# a4988-driver-arduino-shield-v1.net
KiCad netlist of a schematic drawn in EAGLE
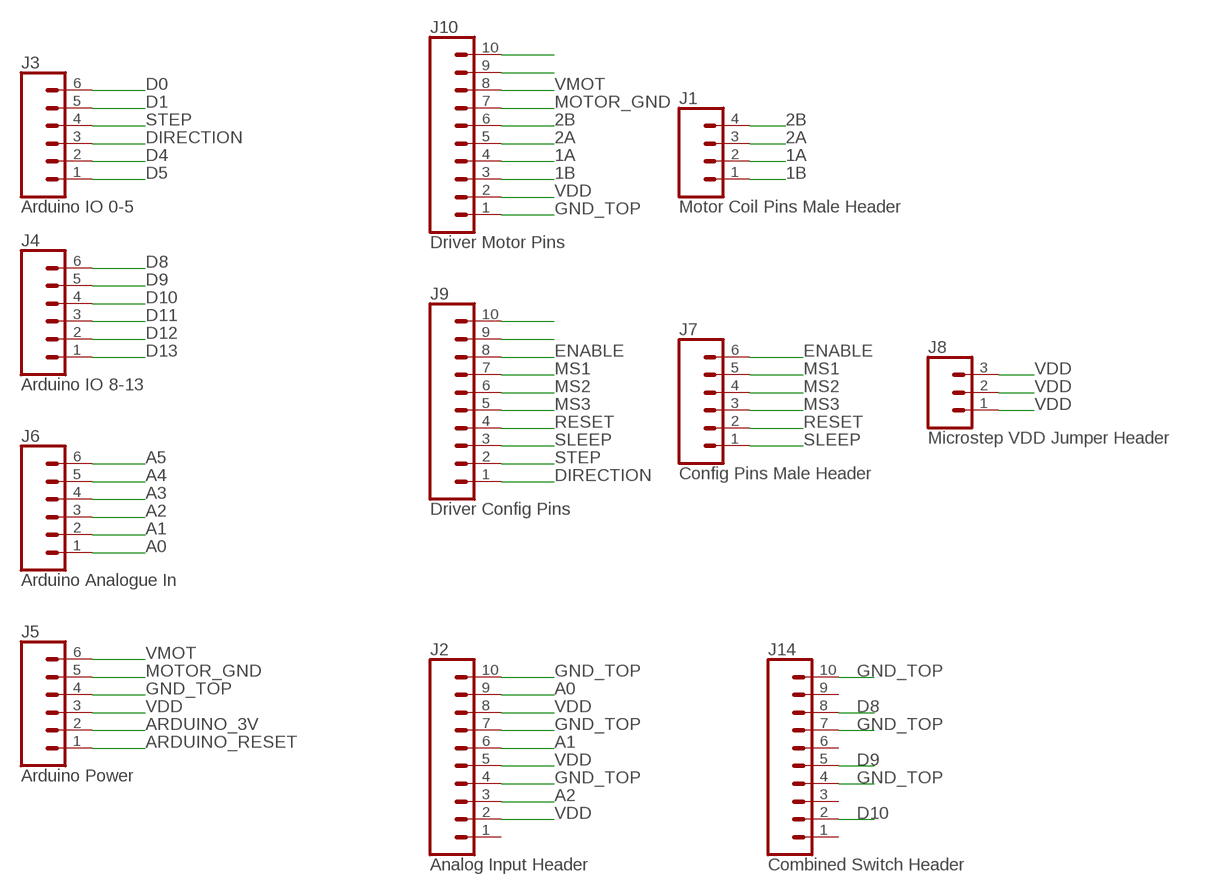
[diagram p0: schematic, sheet 1]

(export (version "E")
  (design (tool "Eeschema 10.0.6"))
  (components
    (comp (ref "J1")
      (value "Motor Coil Pins Male Header")
      (footprint "eagle-import:1X04_LONGPADS")
      (libsource (lib "eagle-import") (part "CONN_04LONGPADS"))
    )
    (comp (ref "J2")
      (value "Analog Input Header")
      (footprint "eagle-import:1X10_SMD_MALE")
      (libsource (lib "eagle-import") (part "CONN_10SMD_MALE"))
    )
    (comp (ref "J3")
      (value "Arduino IO 0-5")
      (footprint "eagle-import:1X06_NO_SILK")
      (libsource (lib "eagle-import") (part "CONN_06NO_SILK_FEMALE_PTH"))
    )
    (comp (ref "J4")
      (value "Arduino IO 8-13")
      (footprint "eagle-import:1X06_NO_SILK")
      (libsource (lib "eagle-import") (part "CONN_06NO_SILK_FEMALE_PTH"))
    )
    (comp (ref "J5")
      (value "Arduino Power")
      (footprint "eagle-import:1X06_NO_SILK")
      (libsource (lib "eagle-import") (part "CONN_06NO_SILK_FEMALE_PTH"))
    )
    (comp (ref "J6")
      (value "Arduino Analogue In")
      (footprint "eagle-import:1X06_NO_SILK")
      (libsource (lib "eagle-import") (part "CONN_06NO_SILK_FEMALE_PTH"))
    )
    (comp (ref "J7")
      (value "Config Pins Male Header")
      (footprint "eagle-import:1X06_SMD_MALE")
      (libsource (lib "eagle-import") (part "CONN_06SMD_MALE"))
    )
    (comp (ref "J8")
      (value "Microstep VDD Jumper Header")
      (footprint "eagle-import:1X03_LONGPADS")
      (libsource (lib "eagle-import") (part "CONN_03LONGPADS"))
    )
    (comp (ref "J9")
      (value "Driver Config Pins")
      (footprint "eagle-import:1X10_SMD_MALE")
      (libsource (lib "eagle-import") (part "CONN_10SMD_MALE"))
    )
    (comp (ref "J10")
      (value "Driver Motor Pins")
      (footprint "eagle-import:1X10_SMD_MALE")
      (libsource (lib "eagle-import") (part "CONN_10SMD_MALE"))
    )
    (comp (ref "J14")
      (value "Combined Switch Header")
      (footprint "eagle-import:1X10_SMD_MALE")
      (libsource (lib "eagle-import") (part "CONN_10SMD_MALE"))
    )
  )
  (nets
    (net (code "1") (name "/1A") (class "Default")
      (node (ref "J1") (pin "2") (pinfunction "2_2") (pintype "passive"))
      (node (ref "J10") (pin "4") (pinfunction "4_4") (pintype "passive"))
    )
    (net (code "2") (name "/1B") (class "Default")
      (node (ref "J1") (pin "1") (pinfunction "1_1") (pintype "passive"))
      (node (ref "J10") (pin "3") (pinfunction "3_3") (pintype "passive"))
    )
    (net (code "3") (name "/2A") (class "Default")
      (node (ref "J1") (pin "3") (pinfunction "3_3") (pintype "passive"))
      (node (ref "J10") (pin "5") (pinfunction "5_5") (pintype "passive"))
    )
    (net (code "4") (name "/2B") (class "Default")
      (node (ref "J1") (pin "4") (pinfunction "4_4") (pintype "passive"))
      (node (ref "J10") (pin "6") (pinfunction "6_6") (pintype "passive"))
    )
    (net (code "5") (name "/A0") (class "Default")
      (node (ref "J2") (pin "9") (pinfunction "9_9") (pintype "passive"))
      (node (ref "J6") (pin "1") (pinfunction "1_1") (pintype "passive"))
    )
    (net (code "6") (name "/A1") (class "Default")
      (node (ref "J2") (pin "6") (pinfunction "6_6") (pintype "passive"))
      (node (ref "J6") (pin "2") (pinfunction "2_2") (pintype "passive"))
    )
    (net (code "7") (name "/A2") (class "Default")
      (node (ref "J2") (pin "3") (pinfunction "3_3") (pintype "passive"))
      (node (ref "J6") (pin "3") (pinfunction "3_3") (pintype "passive"))
    )
    (net (code "8") (name "/A3") (class "Default")
      (node (ref "J6") (pin "4") (pinfunction "4_4") (pintype "passive"))
    )
    (net (code "9") (name "/A4") (class "Default")
      (node (ref "J6") (pin "5") (pinfunction "5_5") (pintype "passive"))
    )
    (net (code "10") (name "/A5") (class "Default")
      (node (ref "J6") (pin "6") (pinfunction "6_6") (pintype "passive"))
    )
    (net (code "11") (name "/ARDUINO_3V") (class "Default")
      (node (ref "J5") (pin "2") (pinfunction "2_2") (pintype "passive"))
    )
    (net (code "12") (name "/ARDUINO_RESET") (class "Default")
      (node (ref "J5") (pin "1") (pinfunction "1_1") (pintype "passive"))
    )
    (net (code "13") (name "/D0") (class "Default")
      (node (ref "J3") (pin "6") (pinfunction "6_6") (pintype "passive"))
    )
    (net (code "14") (name "/D1") (class "Default")
      (node (ref "J3") (pin "5") (pinfunction "5_5") (pintype "passive"))
    )
    (net (code "15") (name "/D4") (class "Default")
      (node (ref "J3") (pin "2") (pinfunction "2_2") (pintype "passive"))
    )
    (net (code "16") (name "/D5") (class "Default")
      (node (ref "J3") (pin "1") (pinfunction "1_1") (pintype "passive"))
    )
    (net (code "17") (name "/D8") (class "Default")
      (node (ref "J14") (pin "8") (pinfunction "8_8") (pintype "passive"))
      (node (ref "J4") (pin "6") (pinfunction "6_6") (pintype "passive"))
    )
    (net (code "18") (name "/D9") (class "Default")
      (node (ref "J14") (pin "5") (pinfunction "5_5") (pintype "passive"))
      (node (ref "J4") (pin "5") (pinfunction "5_5") (pintype "passive"))
    )
    (net (code "19") (name "/D10") (class "Default")
      (node (ref "J14") (pin "2") (pinfunction "2_2") (pintype "passive"))
      (node (ref "J4") (pin "4") (pinfunction "4_4") (pintype "passive"))
    )
    (net (code "20") (name "/D11") (class "Default")
      (node (ref "J4") (pin "3") (pinfunction "3_3") (pintype "passive"))
    )
    (net (code "21") (name "/D12") (class "Default")
      (node (ref "J4") (pin "2") (pinfunction "2_2") (pintype "passive"))
    )
    (net (code "22") (name "/D13") (class "Default")
      (node (ref "J4") (pin "1") (pinfunction "1_1") (pintype "passive"))
    )
    (net (code "23") (name "/DIRECTION") (class "Default")
      (node (ref "J3") (pin "3") (pinfunction "3_3") (pintype "passive"))
      (node (ref "J9") (pin "1") (pinfunction "1_1") (pintype "passive"))
    )
    (net (code "24") (name "/ENABLE") (class "Default")
      (node (ref "J7") (pin "6") (pinfunction "6_6") (pintype "passive"))
      (node (ref "J9") (pin "8") (pinfunction "8_8") (pintype "passive"))
    )
    (net (code "25") (name "/GND_TOP") (class "Default")
      (node (ref "J10") (pin "1") (pinfunction "1_1") (pintype "passive"))
      (node (ref "J14") (pin "10") (pinfunction "10_10") (pintype "passive"))
      (node (ref "J14") (pin "4") (pinfunction "4_4") (pintype "passive"))
      (node (ref "J14") (pin "7") (pinfunction "7_7") (pintype "passive"))
      (node (ref "J2") (pin "10") (pinfunction "10_10") (pintype "passive"))
      (node (ref "J2") (pin "4") (pinfunction "4_4") (pintype "passive"))
      (node (ref "J2") (pin "7") (pinfunction "7_7") (pintype "passive"))
      (node (ref "J5") (pin "4") (pinfunction "4_4") (pintype "passive"))
    )
    (net (code "26") (name "/MOTOR_GND") (class "Default")
      (node (ref "J10") (pin "7") (pinfunction "7_7") (pintype "passive"))
      (node (ref "J5") (pin "5") (pinfunction "5_5") (pintype "passive"))
    )
    (net (code "27") (name "/MS1") (class "Default")
      (node (ref "J7") (pin "5") (pinfunction "5_5") (pintype "passive"))
      (node (ref "J9") (pin "7") (pinfunction "7_7") (pintype "passive"))
    )
    (net (code "28") (name "/MS2") (class "Default")
      (node (ref "J7") (pin "4") (pinfunction "4_4") (pintype "passive"))
      (node (ref "J9") (pin "6") (pinfunction "6_6") (pintype "passive"))
    )
    (net (code "29") (name "/MS3") (class "Default")
      (node (ref "J7") (pin "3") (pinfunction "3_3") (pintype "passive"))
      (node (ref "J9") (pin "5") (pinfunction "5_5") (pintype "passive"))
    )
    (net (code "30") (name "/RESET") (class "Default")
      (node (ref "J7") (pin "2") (pinfunction "2_2") (pintype "passive"))
      (node (ref "J9") (pin "4") (pinfunction "4_4") (pintype "passive"))
    )
    (net (code "31") (name "/SLEEP") (class "Default")
      (node (ref "J7") (pin "1") (pinfunction "1_1") (pintype "passive"))
      (node (ref "J9") (pin "3") (pinfunction "3_3") (pintype "passive"))
    )
    (net (code "32") (name "/STEP") (class "Default")
      (node (ref "J3") (pin "4") (pinfunction "4_4") (pintype "passive"))
      (node (ref "J9") (pin "2") (pinfunction "2_2") (pintype "passive"))
    )
    (net (code "33") (name "/VDD") (class "Default")
      (node (ref "J10") (pin "2") (pinfunction "2_2") (pintype "passive"))
      (node (ref "J2") (pin "2") (pinfunction "2_2") (pintype "passive"))
      (node (ref "J2") (pin "5") (pinfunction "5_5") (pintype "passive"))
      (node (ref "J2") (pin "8") (pinfunction "8_8") (pintype "passive"))
      (node (ref "J5") (pin "3") (pinfunction "3_3") (pintype "passive"))
      (node (ref "J8") (pin "1") (pinfunction "1_1") (pintype "passive"))
      (node (ref "J8") (pin "2") (pinfunction "2_2") (pintype "passive"))
      (node (ref "J8") (pin "3") (pinfunction "3_3") (pintype "passive"))
    )
    (net (code "34") (name "/VMOT") (class "Default")
      (node (ref "J10") (pin "8") (pinfunction "8_8") (pintype "passive"))
      (node (ref "J5") (pin "6") (pinfunction "6_6") (pintype "passive"))
    )
    (net (code "35") (name "unconnected-(J2-Pad1)") (class "Default")
      (node (ref "J2") (pin "1") (pinfunction "1_1") (pintype "passive"))
    )
    (net (code "36") (name "unconnected-(J9-Pad9)") (class "Default")
      (node (ref "J9") (pin "9") (pinfunction "9_9") (pintype "passive"))
    )
    (net (code "37") (name "unconnected-(J9-Pad10)") (class "Default")
      (node (ref "J9") (pin "10") (pinfunction "10_10") (pintype "passive"))
    )
    (net (code "38") (name "unconnected-(J10-Pad9)") (class "Default")
      (node (ref "J10") (pin "9") (pinfunction "9_9") (pintype "passive"))
    )
    (net (code "39") (name "unconnected-(J10-Pad10)") (class "Default")
      (node (ref "J10") (pin "10") (pinfunction "10_10") (pintype "passive"))
    )
    (net (code "40") (name "unconnected-(J14-Pad1)") (class "Default")
      (node (ref "J14") (pin "1") (pinfunction "1_1") (pintype "passive"))
    )
    (net (code "41") (name "unconnected-(J14-Pad3)") (class "Default")
      (node (ref "J14") (pin "3") (pinfunction "3_3") (pintype "passive"))
    )
    (net (code "42") (name "unconnected-(J14-Pad6)") (class "Default")
      (node (ref "J14") (pin "6") (pinfunction "6_6") (pintype "passive"))
    )
    (net (code "43") (name "unconnected-(J14-Pad9)") (class "Default")
      (node (ref "J14") (pin "9") (pinfunction "9_9") (pintype "passive"))
    )
  )
)
